# LB_BIT_i12_TEMPSENSOR-v02_rev1.net
KiCad netlist of a schematic drawn in EAGLE
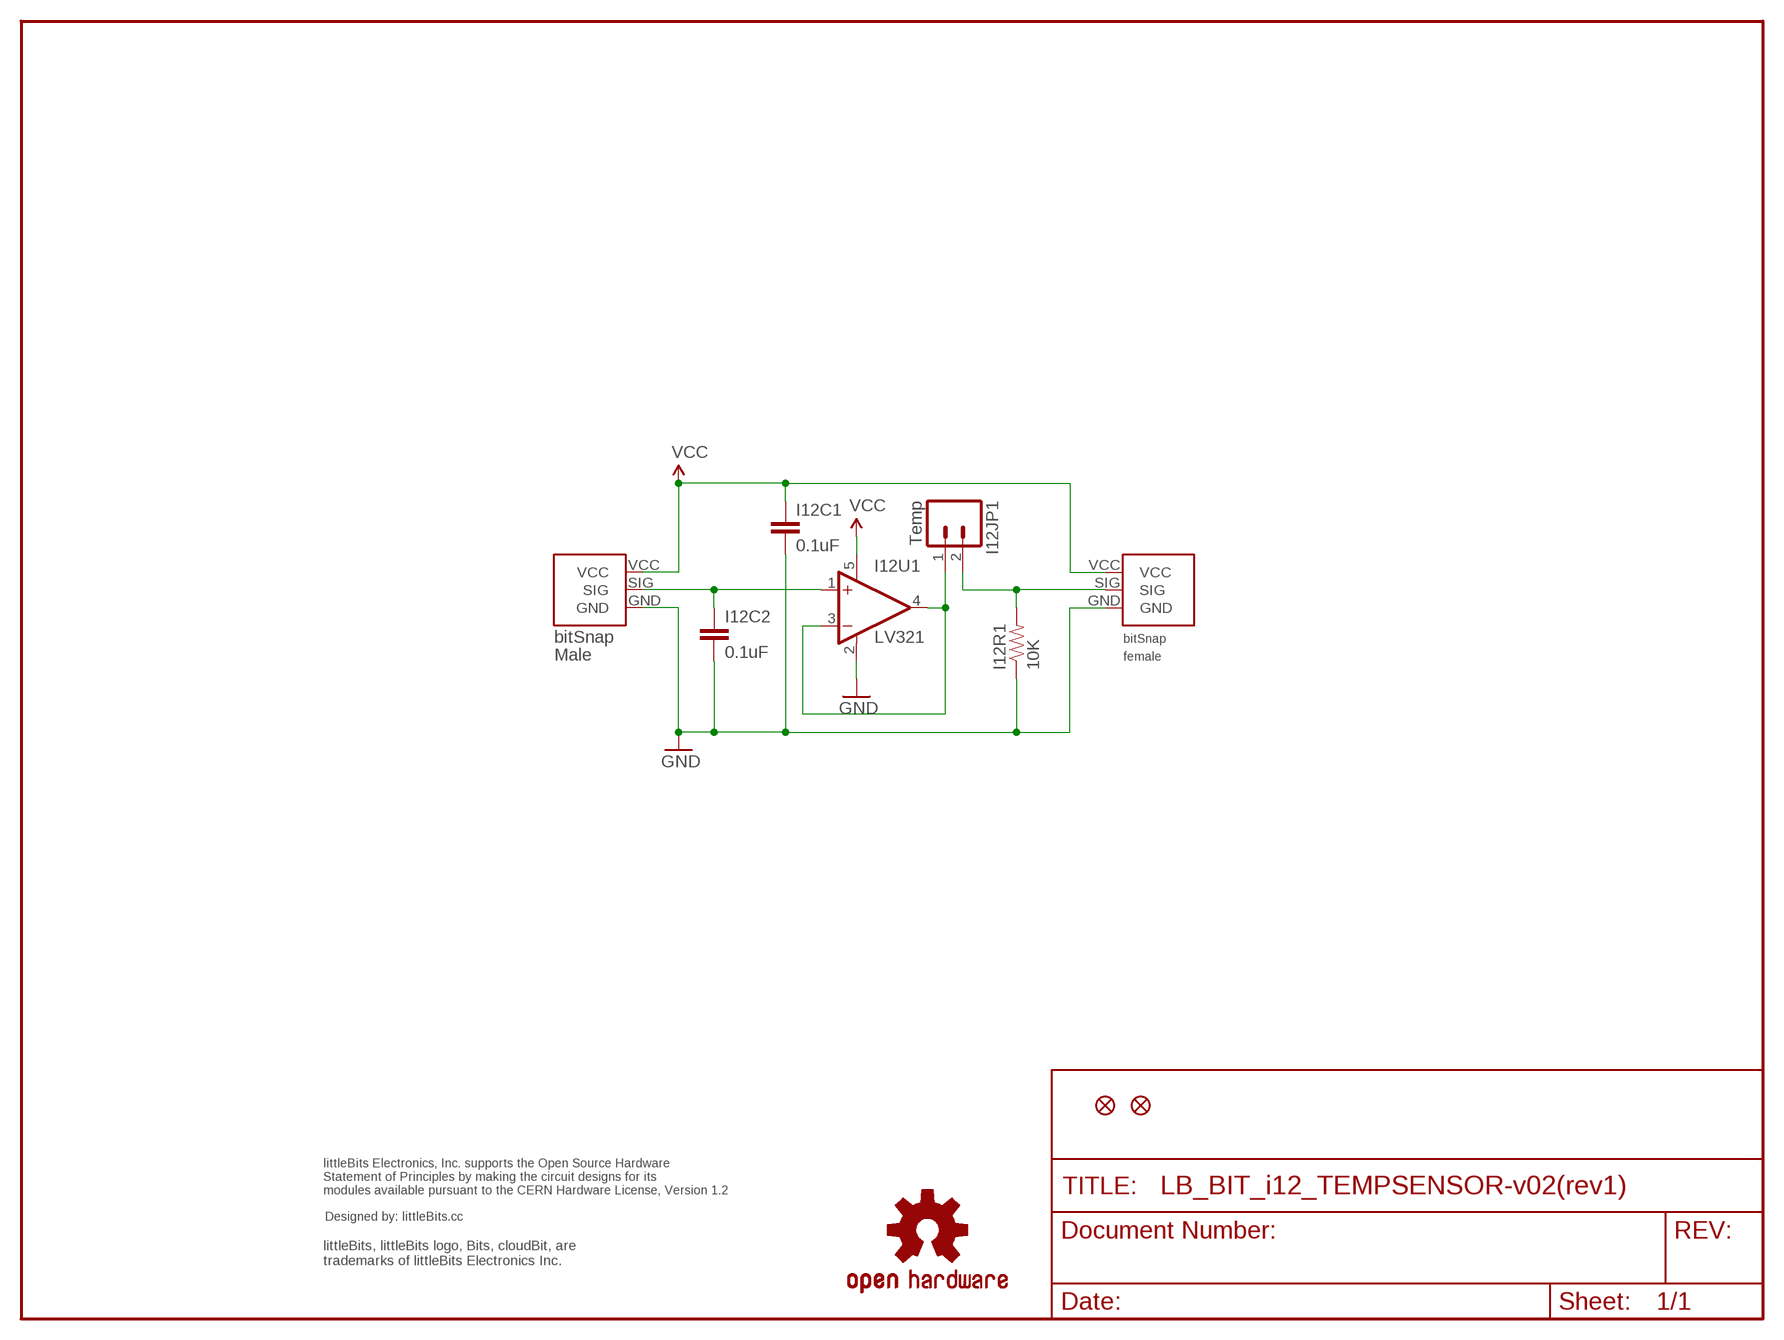
[diagram p0: schematic, sheet 1]

(export (version "E")
  (design (tool "Eeschema 10.0.6"))
  (components
    (comp (ref "I12BSF")
      (value "BITSNAP_FEMALE")
      (footprint "eagle-import:BITSNAP_FEMALE")
      (libsource (lib "eagle-import") (part "BITSNAP_FEMALE"))
    )
    (comp (ref "I12BSM")
      (value "BITSNAP_MALE")
      (footprint "eagle-import:BITSNAP_MALE")
      (libsource (lib "eagle-import") (part "BITSNAP_MALE"))
    )
    (comp (ref "I12C1")
      (value "0.1uF")
      (footprint "eagle-import:0603-CAP")
      (libsource (lib "eagle-import") (part "CAP0603-CAP"))
    )
    (comp (ref "I12C2")
      (value "0.1uF")
      (footprint "eagle-import:0603-CAP")
      (libsource (lib "eagle-import") (part "CAP0603-CAP"))
    )
    (comp (ref "I12JP1")
      (value "Temp")
      (footprint "eagle-import:1X02")
      (libsource (lib "eagle-import") (part "M02PTH"))
    )
    (comp (ref "I12R1")
      (value "10K")
      (footprint "eagle-import:0603-RES")
      (libsource (lib "eagle-import") (part "RESISTOR0603-RES"))
    )
    (comp (ref "I12U1")
      (value "LV321")
      (footprint "eagle-import:SC70-5")
      (libsource (lib "eagle-import") (part "LV321"))
    )
    (comp (ref "JP2")
      (value "FIDUCIAL1X2")
      (footprint "eagle-import:FIDUCIAL-1X2")
      (libsource (lib "eagle-import") (part "FIDUCIAL1X2"))
    )
    (comp (ref "JP3")
      (value "FIDUCIAL1X2")
      (footprint "eagle-import:FIDUCIAL-1X2")
      (libsource (lib "eagle-import") (part "FIDUCIAL1X2"))
    )
    (comp (ref "U$1")
      (value "OSHW-LOGOL")
      (footprint "eagle-import:OSHW-LOGO-L")
      (libsource (lib "eagle-import") (part "OSHW-LOGOL"))
    )
    (comp (ref "U$4")
      (value "OSHWCREDIT")
      (footprint "eagle-import:OSHWCREDIT")
      (libsource (lib "eagle-import") (part "OSHWCREDIT"))
    )
  )
  (nets
    (net (code "1") (name "GND") (class "Default")
      (node (ref "I12BSF") (pin "GND") (pinfunction "GND_GND") (pintype "bidirectional"))
      (node (ref "I12BSM") (pin "GND") (pinfunction "GND_GND") (pintype "bidirectional"))
      (node (ref "I12C1") (pin "2") (pinfunction "2_2") (pintype "passive"))
      (node (ref "I12C2") (pin "2") (pinfunction "2_2") (pintype "passive"))
      (node (ref "I12R1") (pin "1") (pinfunction "1_1") (pintype "passive"))
      (node (ref "I12U1") (pin "2") (pinfunction "V-_2") (pintype "power_in"))
    )
    (net (code "2") (name "Net-(I12BSF-PadSIG)") (class "Default")
      (node (ref "I12BSF") (pin "SIG") (pinfunction "SIG_SIG") (pintype "bidirectional"))
      (node (ref "I12JP1") (pin "2") (pinfunction "2_2") (pintype "passive"))
      (node (ref "I12R1") (pin "2") (pinfunction "2_2") (pintype "passive"))
    )
    (net (code "3") (name "Net-(I12U1-+IN)") (class "Default")
      (node (ref "I12BSM") (pin "SIG") (pinfunction "SIG_SIG") (pintype "bidirectional"))
      (node (ref "I12C2") (pin "1") (pinfunction "1_1") (pintype "passive"))
      (node (ref "I12U1") (pin "1") (pinfunction "+IN_1") (pintype "input"))
    )
    (net (code "4") (name "Net-(I12U1--IN)") (class "Default")
      (node (ref "I12JP1") (pin "1") (pinfunction "1_1") (pintype "passive"))
      (node (ref "I12U1") (pin "3") (pinfunction "-IN_3") (pintype "input"))
      (node (ref "I12U1") (pin "4") (pinfunction "OUT_4") (pintype "output"))
    )
    (net (code "5") (name "VCC") (class "Default")
      (node (ref "I12BSF") (pin "VCC") (pinfunction "VCC_VCC") (pintype "bidirectional"))
      (node (ref "I12BSM") (pin "VCC") (pinfunction "VCC_VCC") (pintype "bidirectional"))
      (node (ref "I12C1") (pin "1") (pinfunction "1_1") (pintype "passive"))
      (node (ref "I12U1") (pin "5") (pinfunction "V+_5") (pintype "power_in"))
    )
  )
)
